# gpio.net
KiCad netlist of a schematic drawn in Altium Designer
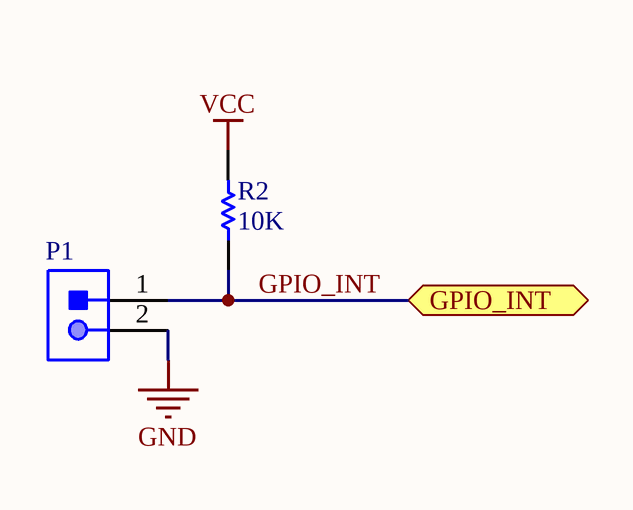
[diagram p0: gpio.SchDoc]

(export (version "E")
  (design (tool "Eeschema 10.0.6"))
  (components
    (comp (ref "P1")
      (value "61300211021")
      (footprint "61300211021")
      (description "THT Angled Pin Header WR-PHD, Pitch 2.54 mm, Single Row, 2 pins")
      (fields (field (name "MANUFACTURER") "Wurth Elektronik") (field (name "PUBLISHER") "WurthElektronik"))
      (libsource (lib "Altium Content Vault") (part "WE-CN-1P-M-R2"))
    )
    (comp (ref "R2")
      (value "10K")
      (footprint "RESC1608X55X30LL15T15")
      (fields (field (name "PART NUMBER") "ERJ-3EKF1002V") (field (name "MANUFACTURER") "Panasonic"))
      (libsource (lib "Altium Content Vault") (part "RES"))
    )
  )
  (nets
    (net (code "1") (name "/GPIO_INT") (class "Default")
      (node (ref "P1") (pin "1") (pinfunction "1_1") (pintype "passive"))
      (node (ref "R2") (pin "1") (pinfunction "1_1") (pintype "passive"))
    )
    (net (code "2") (name "GND") (class "Default")
      (node (ref "P1") (pin "2") (pinfunction "2_2") (pintype "passive"))
    )
    (net (code "3") (name "VCC") (class "Default")
      (node (ref "R2") (pin "2") (pinfunction "2_2") (pintype "passive"))
    )
  )
)
